# FT232.net
KiCad netlist of a schematic drawn in Altium Designer
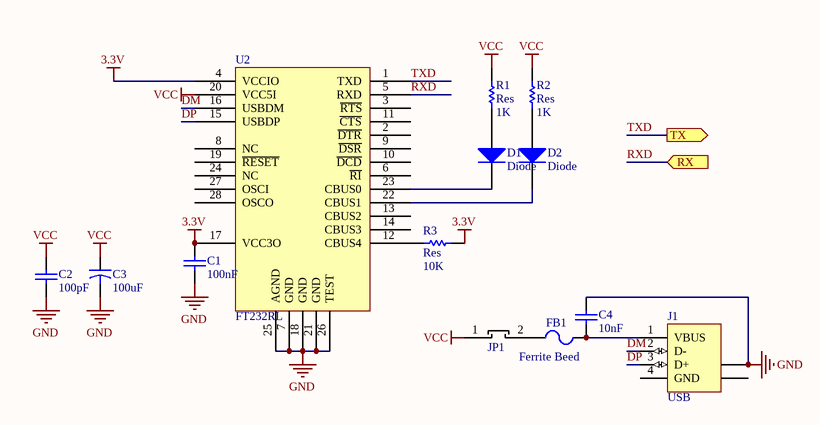
[diagram p0: FT232.SchDoc]

(export (version "E")
  (design (tool "Eeschema 10.0.6"))
  (components
    (comp (ref "C1")
      (value "100nF")
      (footprint "2012[0805]")
      (description "Capacitor")
      (fields (field (name "Comment") "Cap_UP") (field (name "PUBLISHER") "Altium Limited"))
      (libsource (lib "KN2CLib") (part "Cap_UP"))
    )
    (comp (ref "C2")
      (value "100pF")
      (footprint "2012[0805]")
      (description "Capacitor")
      (fields (field (name "Comment") "Cap_UP") (field (name "PUBLISHER") "Altium Limited"))
      (libsource (lib "KN2CLib") (part "Cap_UP"))
    )
    (comp (ref "C3")
      (value "100uF")
      (footprint "2012[0805]")
      (description "Capacitor")
      (fields (field (name "Comment") "Cap_El") (field (name "PUBLISHER") "Altium Limited"))
      (libsource (lib "KN2CLib") (part "Cap_El"))
    )
    (comp (ref "C4")
      (value "10nF")
      (footprint "2012[0805]")
      (description "Capacitor")
      (fields (field (name "Comment") "Cap_UP") (field (name "PUBLISHER") "Altium Limited"))
      (libsource (lib "KN2CLib") (part "Cap_UP"))
    )
    (comp (ref "D1")
      (value "Diode")
      (footprint "2012[0805]")
      (description "1 Amp General Purpose Rectifier")
      (fields (field (name "PUBLISHER") "Altium Limited"))
      (libsource (lib "KN2CLib") (part "Diode"))
    )
    (comp (ref "D2")
      (value "Diode")
      (footprint "2012[0805]")
      (description "1 Amp General Purpose Rectifier")
      (fields (field (name "PUBLISHER") "Altium Limited"))
      (libsource (lib "KN2CLib") (part "Diode"))
    )
    (comp (ref "FB1")
      (value "Ferrite Beed")
      (footprint "2012[0805]")
      (fields (field (name "PUBLISHER") "Altium Limited"))
      (libsource (lib "KN2CLib") (part "Ferrite Beed"))
    )
    (comp (ref "J1")
      (value "USB")
      (footprint "USB_Mini")
      (description "USB 1.1, Right Angle, Thru-Hole, A Type, Receptacle, 4 Position, Black")
      (fields (field (name "PUBLISHER") "Altium Limited"))
      (libsource (lib "KN2CLib") (part "USB"))
    )
    (comp (ref "JP1") (value "JUMPER") (footprint "HDR1X2") (libsource (lib "KN2CLib") (part "JUMPER")))
    (comp (ref "R1")
      (value "Res")
      (footprint "2012[0805]")
      (description "Semiconductor Resistor")
      (fields (field (name "ALTIUM_VALUE") "1K") (field (name "PUBLISHER") "Altium Limited"))
      (libsource (lib "KN2CLib") (part "Res"))
    )
    (comp (ref "R2")
      (value "Res")
      (footprint "2012[0805]")
      (description "Semiconductor Resistor")
      (fields (field (name "ALTIUM_VALUE") "1K") (field (name "PUBLISHER") "Altium Limited"))
      (libsource (lib "KN2CLib") (part "Res"))
    )
    (comp (ref "R3")
      (value "Res")
      (footprint "2012[0805]")
      (description "Semiconductor Resistor")
      (fields (field (name "ALTIUM_VALUE") "10K") (field (name "PUBLISHER") "Altium Limited"))
      (libsource (lib "KN2CLib") (part "Res"))
    )
    (comp (ref "U2") (value "FT232RL") (footprint "SSOP28") (libsource (lib "KN2CLib") (part "FT232RL")))
  )
  (nets
    (net (code "1") (name "/DM") (class "Default")
      (node (ref "J1") (pin "2") (pinfunction "D-_2") (pintype "bidirectional"))
      (node (ref "U2") (pin "16") (pinfunction "USBDM_16") (pintype "passive"))
    )
    (net (code "2") (name "/DP") (class "Default")
      (node (ref "J1") (pin "3") (pinfunction "D+_3") (pintype "bidirectional"))
      (node (ref "U2") (pin "15") (pinfunction "USBDP_15") (pintype "passive"))
    )
    (net (code "3") (name "/RXD") (class "Default")
      (node (ref "U2") (pin "5") (pinfunction "RXD_5") (pintype "passive"))
    )
    (net (code "4") (name "/TXD") (class "Default")
      (node (ref "U2") (pin "1") (pinfunction "TXD_1") (pintype "passive"))
    )
    (net (code "5") (name "3.3V") (class "Default")
      (node (ref "C1") (pin "2") (pinfunction "2_2") (pintype "passive"))
      (node (ref "R3") (pin "2") (pinfunction "2_2") (pintype "passive"))
      (node (ref "U2") (pin "17") (pinfunction "VCC3O_17") (pintype "passive"))
      (node (ref "U2") (pin "4") (pinfunction "VCCIO_4") (pintype "passive"))
    )
    (net (code "6") (name "GND") (class "Default")
      (node (ref "C1") (pin "1") (pinfunction "1_1") (pintype "passive"))
      (node (ref "C2") (pin "1") (pinfunction "1_1") (pintype "passive"))
      (node (ref "C3") (pin "2") (pinfunction "2_2") (pintype "passive"))
      (node (ref "C4") (pin "1") (pinfunction "1_1") (pintype "passive"))
      (node (ref "J1") (pin "5") (pinfunction "SHLD_5") (pintype "passive"))
      (node (ref "U2") (pin "18") (pinfunction "GND_18") (pintype "passive"))
      (node (ref "U2") (pin "21") (pinfunction "GND_21") (pintype "passive"))
      (node (ref "U2") (pin "25") (pinfunction "AGND_25") (pintype "passive"))
      (node (ref "U2") (pin "26") (pinfunction "TEST_26") (pintype "passive"))
      (node (ref "U2") (pin "7") (pinfunction "GND_7") (pintype "passive"))
    )
    (net (code "7") (name "Net-(D1-A)") (class "Default")
      (node (ref "D1") (pin "1") (pinfunction "A_1") (pintype "passive"))
      (node (ref "R1") (pin "1") (pinfunction "1_1") (pintype "passive"))
    )
    (net (code "8") (name "Net-(D1-K)") (class "Default")
      (node (ref "D1") (pin "2") (pinfunction "K_2") (pintype "passive"))
      (node (ref "U2") (pin "23") (pinfunction "CBUS0_23") (pintype "passive"))
    )
    (net (code "9") (name "Net-(D2-A)") (class "Default")
      (node (ref "D2") (pin "1") (pinfunction "A_1") (pintype "passive"))
      (node (ref "R2") (pin "1") (pinfunction "1_1") (pintype "passive"))
    )
    (net (code "10") (name "Net-(D2-K)") (class "Default")
      (node (ref "D2") (pin "2") (pinfunction "K_2") (pintype "passive"))
      (node (ref "U2") (pin "22") (pinfunction "CBUS1_22") (pintype "passive"))
    )
    (net (code "11") (name "Net-(FB1-Pad1)") (class "Default")
      (node (ref "FB1") (pin "1") (pinfunction "1_1") (pintype "passive"))
      (node (ref "JP1") (pin "2") (pinfunction "2_2") (pintype "passive"))
    )
    (net (code "12") (name "Net-(J1-VBUS)") (class "Default")
      (node (ref "C4") (pin "2") (pinfunction "2_2") (pintype "passive"))
      (node (ref "FB1") (pin "2") (pinfunction "2_2") (pintype "passive"))
      (node (ref "J1") (pin "1") (pinfunction "VBUS_1") (pintype "power_in"))
    )
    (net (code "13") (name "Net-(U2-CBUS4)") (class "Default")
      (node (ref "R3") (pin "1") (pinfunction "1_1") (pintype "passive"))
      (node (ref "U2") (pin "12") (pinfunction "CBUS4_12") (pintype "passive"))
    )
    (net (code "14") (name "VCC") (class "Default")
      (node (ref "C2") (pin "2") (pinfunction "2_2") (pintype "passive"))
      (node (ref "C3") (pin "1") (pinfunction "1_1") (pintype "passive"))
      (node (ref "JP1") (pin "1") (pinfunction "1_1") (pintype "passive"))
      (node (ref "R1") (pin "2") (pinfunction "2_2") (pintype "passive"))
      (node (ref "R2") (pin "2") (pinfunction "2_2") (pintype "passive"))
      (node (ref "U2") (pin "20") (pinfunction "VCC5I_20") (pintype "passive"))
    )
    (net (code "15") (name "unconnected-(J1-GND-Pad4)") (class "Default")
      (node (ref "J1") (pin "4") (pinfunction "GND_4") (pintype "power_in"))
    )
    (net (code "16") (name "unconnected-(J1-SHLD-Pad6)") (class "Default")
      (node (ref "J1") (pin "6") (pinfunction "SHLD_6") (pintype "passive"))
    )
    (net (code "17") (name "unconnected-(U2-CBUS2-Pad13)") (class "Default")
      (node (ref "U2") (pin "13") (pinfunction "CBUS2_13") (pintype "passive"))
    )
    (net (code "18") (name "unconnected-(U2-CBUS3-Pad14)") (class "Default")
      (node (ref "U2") (pin "14") (pinfunction "CBUS3_14") (pintype "passive"))
    )
    (net (code "19") (name "unconnected-(U2-NC-Pad8)") (class "Default")
      (node (ref "U2") (pin "8") (pinfunction "NC_8") (pintype "passive"))
    )
    (net (code "20") (name "unconnected-(U2-NC-Pad24)") (class "Default")
      (node (ref "U2") (pin "24") (pinfunction "NC_24") (pintype "passive"))
    )
    (net (code "21") (name "unconnected-(U2-OSCI-Pad27)") (class "Default")
      (node (ref "U2") (pin "27") (pinfunction "OSCI_27") (pintype "passive"))
    )
    (net (code "22") (name "unconnected-(U2-OSCO-Pad28)") (class "Default")
      (node (ref "U2") (pin "28") (pinfunction "OSCO_28") (pintype "passive"))
    )
    (net (code "23") (name "unconnected-(U2-~{CTS}-Pad11)") (class "Default")
      (node (ref "U2") (pin "11") (pinfunction "~{CTS}_11") (pintype "passive"))
    )
    (net (code "24") (name "unconnected-(U2-~{DCD}-Pad10)") (class "Default")
      (node (ref "U2") (pin "10") (pinfunction "~{DCD}_10") (pintype "passive"))
    )
    (net (code "25") (name "unconnected-(U2-~{DSR}-Pad9)") (class "Default")
      (node (ref "U2") (pin "9") (pinfunction "~{DSR}_9") (pintype "passive"))
    )
    (net (code "26") (name "unconnected-(U2-~{DTR}-Pad2)") (class "Default")
      (node (ref "U2") (pin "2") (pinfunction "~{DTR}_2") (pintype "passive"))
    )
    (net (code "27") (name "unconnected-(U2-~{RESET}-Pad19)") (class "Default")
      (node (ref "U2") (pin "19") (pinfunction "~{RESET}_19") (pintype "passive"))
    )
    (net (code "28") (name "unconnected-(U2-~{RI}-Pad6)") (class "Default")
      (node (ref "U2") (pin "6") (pinfunction "~{RI}_6") (pintype "passive"))
    )
    (net (code "29") (name "unconnected-(U2-~{RTS}-Pad3)") (class "Default")
      (node (ref "U2") (pin "3") (pinfunction "~{RTS}_3") (pintype "passive"))
    )
  )
)
